# power_unit.net
KiCad netlist of a schematic drawn in Altium Designer
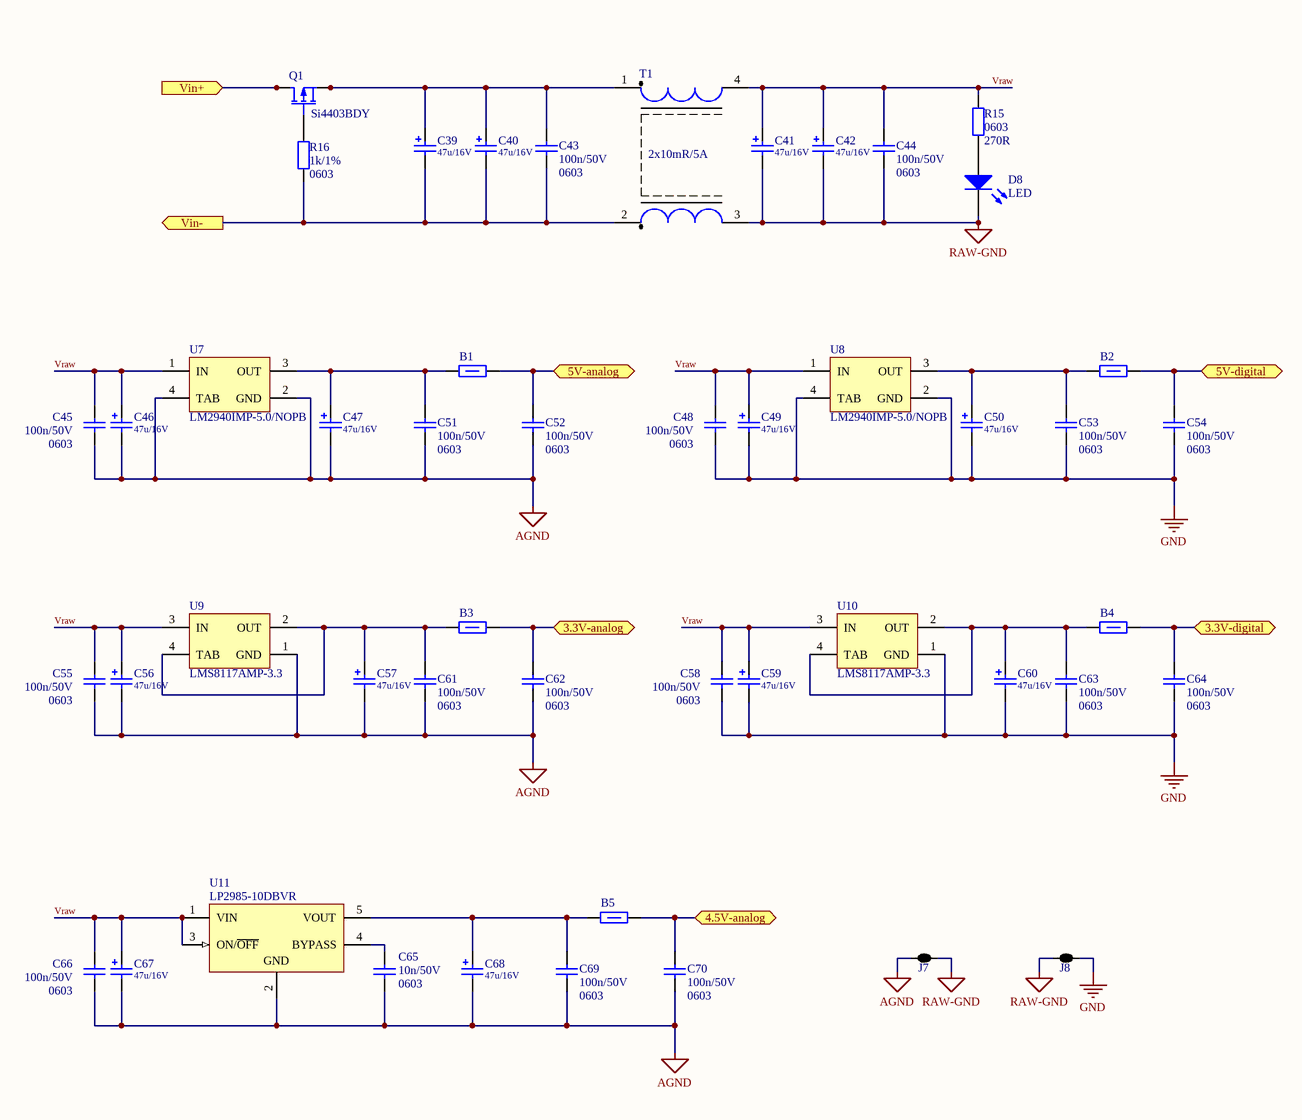
[diagram p0: power_unit.SchDoc]

(export (version "E")
  (design (tool "Eeschema 10.0.6"))
  (components
    (comp (ref "B1")
      (value "120R/100MHz")
      (footprint "SMD_FerriteBead_1206")
      (description "Ferrite bead, 1206, 0.02HM, 3.5A.")
      (fields (field (name "MANUFACTURER") "Murata") (field (name "MANUFACTURERPARTNUMBER") "BLM31PG121SH1L"))
      (libsource (lib "inductors") (part "BLM31PG121SH1L"))
    )
    (comp (ref "B2")
      (value "120R/100MHz")
      (footprint "SMD_FerriteBead_1206")
      (description "Ferrite bead, 1206, 0.02HM, 3.5A.")
      (fields (field (name "MANUFACTURER") "Murata") (field (name "MANUFACTURERPARTNUMBER") "BLM31PG121SH1L"))
      (libsource (lib "inductors") (part "BLM31PG121SH1L"))
    )
    (comp (ref "B3")
      (value "120R/100MHz")
      (footprint "SMD_FerriteBead_1206")
      (description "Ferrite bead, 1206, 0.02HM, 3.5A.")
      (fields (field (name "MANUFACTURER") "Murata") (field (name "MANUFACTURERPARTNUMBER") "BLM31PG121SH1L"))
      (libsource (lib "inductors") (part "BLM31PG121SH1L"))
    )
    (comp (ref "B4")
      (value "120R/100MHz")
      (footprint "SMD_FerriteBead_1206")
      (description "Ferrite bead, 1206, 0.02HM, 3.5A.")
      (fields (field (name "MANUFACTURER") "Murata") (field (name "MANUFACTURERPARTNUMBER") "BLM31PG121SH1L"))
      (libsource (lib "inductors") (part "BLM31PG121SH1L"))
    )
    (comp (ref "B5")
      (value "120R/100MHz")
      (footprint "SMD_FerriteBead_1206")
      (description "Ferrite bead, 1206, 0.02HM, 3.5A.")
      (fields (field (name "MANUFACTURER") "Murata") (field (name "MANUFACTURERPARTNUMBER") "BLM31PG121SH1L"))
      (libsource (lib "inductors") (part "BLM31PG121SH1L"))
    )
    (comp (ref "C39")
      (value "47u/16V")
      (footprint "Tantalum_cap_B")
      (description "Tantalum Capacitor")
      (libsource (lib "GG") (part "Cap Tantalum"))
    )
    (comp (ref "C40")
      (value "47u/16V")
      (footprint "Tantalum_cap_B")
      (description "Tantalum Capacitor")
      (libsource (lib "GG") (part "Cap Tantalum"))
    )
    (comp (ref "C41")
      (value "47u/16V")
      (footprint "Tantalum_cap_B")
      (description "Tantalum Capacitor")
      (libsource (lib "GG") (part "Cap Tantalum"))
    )
    (comp (ref "C42")
      (value "47u/16V")
      (footprint "Tantalum_cap_B")
      (description "Tantalum Capacitor")
      (libsource (lib "GG") (part "Cap Tantalum"))
    )
    (comp (ref "C43")
      (value "100n/50V")
      (footprint "SMD_Capacitor_0603")
      (description "Ceramic Cap Kemet COTS 100n/50V X7R 0603")
      (fields
        (field (name "MANUFACTURER") "Kemet")
        (field (name "MANUFACTURERPARTNUMBER") "C0603T104K5RALTU")
        (field (name "PACKAGE") "0603")
      )
      (libsource (lib "capacitors") (part "Cer_C0603T104K5RALTU"))
    )
    (comp (ref "C44")
      (value "100n/50V")
      (footprint "SMD_Capacitor_0603")
      (description "Ceramic Cap Kemet COTS 100n/50V X7R 0603")
      (fields
        (field (name "MANUFACTURER") "Kemet")
        (field (name "MANUFACTURERPARTNUMBER") "C0603T104K5RALTU")
        (field (name "PACKAGE") "0603")
      )
      (libsource (lib "capacitors") (part "Cer_C0603T104K5RALTU"))
    )
    (comp (ref "C45")
      (value "100n/50V")
      (footprint "SMD_Capacitor_0603")
      (description "Ceramic Cap Kemet COTS 100n/50V X7R 0603")
      (fields
        (field (name "MANUFACTURER") "Kemet")
        (field (name "MANUFACTURERPARTNUMBER") "C0603T104K5RALTU")
        (field (name "PACKAGE") "0603")
      )
      (libsource (lib "capacitors") (part "Cer_C0603T104K5RALTU"))
    )
    (comp (ref "C46")
      (value "47u/16V")
      (footprint "Tantalum_cap_B")
      (description "Tantalum Capacitor")
      (libsource (lib "GG") (part "Cap Tantalum"))
    )
    (comp (ref "C47")
      (value "47u/16V")
      (footprint "Tantalum_cap_B")
      (description "Tantalum Capacitor")
      (libsource (lib "GG") (part "Cap Tantalum"))
    )
    (comp (ref "C48")
      (value "100n/50V")
      (footprint "SMD_Capacitor_0603")
      (description "Ceramic Cap Kemet COTS 100n/50V X7R 0603")
      (fields
        (field (name "MANUFACTURER") "Kemet")
        (field (name "MANUFACTURERPARTNUMBER") "C0603T104K5RALTU")
        (field (name "PACKAGE") "0603")
      )
      (libsource (lib "capacitors") (part "Cer_C0603T104K5RALTU"))
    )
    (comp (ref "C49")
      (value "47u/16V")
      (footprint "Tantalum_cap_B")
      (description "Tantalum Capacitor")
      (libsource (lib "GG") (part "Cap Tantalum"))
    )
    (comp (ref "C50")
      (value "47u/16V")
      (footprint "Tantalum_cap_B")
      (description "Tantalum Capacitor")
      (libsource (lib "GG") (part "Cap Tantalum"))
    )
    (comp (ref "C51")
      (value "100n/50V")
      (footprint "SMD_Capacitor_0603")
      (description "Ceramic Cap Kemet COTS 100n/50V X7R 0603")
      (fields
        (field (name "MANUFACTURER") "Kemet")
        (field (name "MANUFACTURERPARTNUMBER") "C0603T104K5RALTU")
        (field (name "PACKAGE") "0603")
      )
      (libsource (lib "capacitors") (part "Cer_C0603T104K5RALTU"))
    )
    (comp (ref "C52")
      (value "100n/50V")
      (footprint "SMD_Capacitor_0603")
      (description "Ceramic Cap Kemet COTS 100n/50V X7R 0603")
      (fields
        (field (name "MANUFACTURER") "Kemet")
        (field (name "MANUFACTURERPARTNUMBER") "C0603T104K5RALTU")
        (field (name "PACKAGE") "0603")
      )
      (libsource (lib "capacitors") (part "Cer_C0603T104K5RALTU"))
    )
    (comp (ref "C53")
      (value "100n/50V")
      (footprint "SMD_Capacitor_0603")
      (description "Ceramic Cap Kemet COTS 100n/50V X7R 0603")
      (fields
        (field (name "MANUFACTURER") "Kemet")
        (field (name "MANUFACTURERPARTNUMBER") "C0603T104K5RALTU")
        (field (name "PACKAGE") "0603")
      )
      (libsource (lib "capacitors") (part "Cer_C0603T104K5RALTU"))
    )
    (comp (ref "C54")
      (value "100n/50V")
      (footprint "SMD_Capacitor_0603")
      (description "Ceramic Cap Kemet COTS 100n/50V X7R 0603")
      (fields
        (field (name "MANUFACTURER") "Kemet")
        (field (name "MANUFACTURERPARTNUMBER") "C0603T104K5RALTU")
        (field (name "PACKAGE") "0603")
      )
      (libsource (lib "capacitors") (part "Cer_C0603T104K5RALTU"))
    )
    (comp (ref "C55")
      (value "100n/50V")
      (footprint "SMD_Capacitor_0603")
      (description "Ceramic Cap Kemet COTS 100n/50V X7R 0603")
      (fields
        (field (name "MANUFACTURER") "Kemet")
        (field (name "MANUFACTURERPARTNUMBER") "C0603T104K5RALTU")
        (field (name "PACKAGE") "0603")
      )
      (libsource (lib "capacitors") (part "Cer_C0603T104K5RALTU"))
    )
    (comp (ref "C56")
      (value "47u/16V")
      (footprint "Tantalum_cap_B")
      (description "Tantalum Capacitor")
      (libsource (lib "GG") (part "Cap Tantalum"))
    )
    (comp (ref "C57")
      (value "47u/16V")
      (footprint "Tantalum_cap_B")
      (description "Tantalum Capacitor")
      (libsource (lib "GG") (part "Cap Tantalum"))
    )
    (comp (ref "C58")
      (value "100n/50V")
      (footprint "SMD_Capacitor_0603")
      (description "Ceramic Cap Kemet COTS 100n/50V X7R 0603")
      (fields
        (field (name "MANUFACTURER") "Kemet")
        (field (name "MANUFACTURERPARTNUMBER") "C0603T104K5RALTU")
        (field (name "PACKAGE") "0603")
      )
      (libsource (lib "capacitors") (part "Cer_C0603T104K5RALTU"))
    )
    (comp (ref "C59")
      (value "47u/16V")
      (footprint "Tantalum_cap_B")
      (description "Tantalum Capacitor")
      (libsource (lib "GG") (part "Cap Tantalum"))
    )
    (comp (ref "C60")
      (value "47u/16V")
      (footprint "Tantalum_cap_B")
      (description "Tantalum Capacitor")
      (libsource (lib "GG") (part "Cap Tantalum"))
    )
    (comp (ref "C61")
      (value "100n/50V")
      (footprint "SMD_Capacitor_0603")
      (description "Ceramic Cap Kemet COTS 100n/50V X7R 0603")
      (fields
        (field (name "MANUFACTURER") "Kemet")
        (field (name "MANUFACTURERPARTNUMBER") "C0603T104K5RALTU")
        (field (name "PACKAGE") "0603")
      )
      (libsource (lib "capacitors") (part "Cer_C0603T104K5RALTU"))
    )
    (comp (ref "C62")
      (value "100n/50V")
      (footprint "SMD_Capacitor_0603")
      (description "Ceramic Cap Kemet COTS 100n/50V X7R 0603")
      (fields
        (field (name "MANUFACTURER") "Kemet")
        (field (name "MANUFACTURERPARTNUMBER") "C0603T104K5RALTU")
        (field (name "PACKAGE") "0603")
      )
      (libsource (lib "capacitors") (part "Cer_C0603T104K5RALTU"))
    )
    (comp (ref "C63")
      (value "100n/50V")
      (footprint "SMD_Capacitor_0603")
      (description "Ceramic Cap Kemet COTS 100n/50V X7R 0603")
      (fields
        (field (name "MANUFACTURER") "Kemet")
        (field (name "MANUFACTURERPARTNUMBER") "C0603T104K5RALTU")
        (field (name "PACKAGE") "0603")
      )
      (libsource (lib "capacitors") (part "Cer_C0603T104K5RALTU"))
    )
    (comp (ref "C64")
      (value "100n/50V")
      (footprint "SMD_Capacitor_0603")
      (description "Ceramic Cap Kemet COTS 100n/50V X7R 0603")
      (fields
        (field (name "MANUFACTURER") "Kemet")
        (field (name "MANUFACTURERPARTNUMBER") "C0603T104K5RALTU")
        (field (name "PACKAGE") "0603")
      )
      (libsource (lib "capacitors") (part "Cer_C0603T104K5RALTU"))
    )
    (comp (ref "C65")
      (value "10n/50V")
      (footprint "SMD_Capacitor_0603")
      (description "Cap")
      (fields (field (name "PACKAGE") "0603"))
      (libsource (lib "capacitors") (part "Cap"))
    )
    (comp (ref "C66")
      (value "100n/50V")
      (footprint "SMD_Capacitor_0603")
      (description "Ceramic Cap Kemet COTS 100n/50V X7R 0603")
      (fields
        (field (name "MANUFACTURER") "Kemet")
        (field (name "MANUFACTURERPARTNUMBER") "C0603T104K5RALTU")
        (field (name "PACKAGE") "0603")
      )
      (libsource (lib "capacitors") (part "Cer_C0603T104K5RALTU"))
    )
    (comp (ref "C67")
      (value "47u/16V")
      (footprint "Tantalum_cap_B")
      (description "Tantalum Capacitor")
      (libsource (lib "GG") (part "Cap Tantalum"))
    )
    (comp (ref "C68")
      (value "47u/16V")
      (footprint "Tantalum_cap_B")
      (description "Tantalum Capacitor")
      (libsource (lib "GG") (part "Cap Tantalum"))
    )
    (comp (ref "C69")
      (value "100n/50V")
      (footprint "SMD_Capacitor_0603")
      (description "Ceramic Cap Kemet COTS 100n/50V X7R 0603")
      (fields
        (field (name "MANUFACTURER") "Kemet")
        (field (name "MANUFACTURERPARTNUMBER") "C0603T104K5RALTU")
        (field (name "PACKAGE") "0603")
      )
      (libsource (lib "capacitors") (part "Cer_C0603T104K5RALTU"))
    )
    (comp (ref "C70")
      (value "100n/50V")
      (footprint "SMD_Capacitor_0603")
      (description "Ceramic Cap Kemet COTS 100n/50V X7R 0603")
      (fields
        (field (name "MANUFACTURER") "Kemet")
        (field (name "MANUFACTURERPARTNUMBER") "C0603T104K5RALTU")
        (field (name "PACKAGE") "0603")
      )
      (libsource (lib "capacitors") (part "Cer_C0603T104K5RALTU"))
    )
    (comp (ref "D8")
      (value "LED")
      (footprint "LED 0805 RED")
      (description "Typical BLUE SiC LED")
      (fields (field (name "PUBLISHER") "Altium Limited"))
      (libsource (lib "Miscellaneous Devices") (part "LED3"))
    )
    (comp (ref "J7")
      (value "2 way net tie junction")
      (footprint "2way_MP")
      (libsource (lib "NetTieLib") (part "2way"))
    )
    (comp (ref "J8")
      (value "2 way net tie junction")
      (footprint "2way_MP")
      (libsource (lib "NetTieLib") (part "2way"))
    )
    (comp (ref "Q1")
      (value "Si4403BDY")
      (footprint "SOIC-8_M")
      (description "P-Channel 1.8 V (G-S) MOSFET")
      (libsource (lib "GG") (part "Si4403BDY"))
    )
    (comp (ref "R15")
      (value "0603")
      (footprint "SMD_Resistor_0603")
      (description "Resistor")
      (fields (field (name "ALTIUM_VALUE") "270R") (field (name "PUBLISHER") "Altium Limited"))
      (libsource (lib "Miscellaneous Devices") (part "Res2"))
    )
    (comp (ref "R16")
      (value "1k/1%")
      (footprint "SMD_Resistor_0603")
      (description "1k/1% Vishay CRCW 0603 Resistor. 100mW, 100ppm, 75V.")
      (fields
        (field (name "MANUFACTURER") "Vishay")
        (field (name "MANUFACTURERPARTNUMBER") "CRCW06031K00FKxxxx")
        (field (name "PACKAGE") "0603")
      )
      (libsource (lib "resistors") (part "CRCW06031K00FKxxxx"))
    )
    (comp (ref "T1")
      (value "2x10mR/5A")
      (footprint "TDK_ACM7060")
      (description "TDK ACM7060-301 Common Mode Choke")
      (fields
        (field (name "MANUFACTURER") "TDK")
        (field (name "MANUFACTURERPARTNUMBER") "ACM7060-301-2PL-TL01")
      )
      (libsource (lib "GG") (part "ACM7060-301-2PL-TL01"))
    )
    (comp (ref "U7")
      (value "LM2940IMP-5.0/NOPB")
      (footprint "MP04A_N")
      (description "1A Low Dropout Regulator, 4-pin SOT-223, Pb-Free")
      (fields (field (name "MANUFACTURER") "National Semiconductor"))
      (libsource (lib "National Semiconductor LDO") (part "LM2940IMP-5.0/NOPB"))
    )
    (comp (ref "U8")
      (value "LM2940IMP-5.0/NOPB")
      (footprint "MP04A_N")
      (description "1A Low Dropout Regulator, 4-pin SOT-223, Pb-Free")
      (fields (field (name "MANUFACTURER") "National Semiconductor"))
      (libsource (lib "National Semiconductor LDO") (part "LM2940IMP-5.0/NOPB"))
    )
    (comp (ref "U9")
      (value "LMS8117AMP-3.3")
      (footprint "MP04A_M")
      (description "1A Low-Dropout Linear Regulator, 4-pin SOT-223")
      (fields (field (name "MANUFACTURER") "National Semiconductor"))
      (libsource (lib "National Semiconductor LDO") (part "LMS8117AMP-3.3"))
    )
    (comp (ref "U10")
      (value "LMS8117AMP-3.3")
      (footprint "MP04A_M")
      (description "1A Low-Dropout Linear Regulator, 4-pin SOT-223")
      (fields (field (name "MANUFACTURER") "National Semiconductor"))
      (libsource (lib "National Semiconductor LDO") (part "LMS8117AMP-3.3"))
    )
    (comp (ref "U11")
      (value "LP2985-10DBVR")
      (footprint "TI-DBV5_N")
      (fields (field (name "MANUFACTURER") "Texas Instruments"))
      (libsource (lib "TI Power Management Linear Regulator Single Channel LDO (0-350mA)") (part "LP2985-10DBVR"))
    )
  )
  (nets
    (net (code "1") (name "/3.3V-analog") (class "Default")
      (node (ref "B3") (pin "2") (pinfunction "2_2") (pintype "passive"))
      (node (ref "C62") (pin "1") (pinfunction "1_1") (pintype "passive"))
    )
    (net (code "2") (name "/3.3V-digital") (class "Default")
      (node (ref "B4") (pin "2") (pinfunction "2_2") (pintype "passive"))
      (node (ref "C64") (pin "1") (pinfunction "1_1") (pintype "passive"))
    )
    (net (code "3") (name "/4.5V-analog") (class "Default")
      (node (ref "B5") (pin "2") (pinfunction "2_2") (pintype "passive"))
      (node (ref "C70") (pin "1") (pinfunction "1_1") (pintype "passive"))
    )
    (net (code "4") (name "/5V-analog") (class "Default")
      (node (ref "B1") (pin "2") (pinfunction "2_2") (pintype "passive"))
      (node (ref "C52") (pin "1") (pinfunction "1_1") (pintype "passive"))
    )
    (net (code "5") (name "/5V-digital") (class "Default")
      (node (ref "B2") (pin "2") (pinfunction "2_2") (pintype "passive"))
      (node (ref "C54") (pin "1") (pinfunction "1_1") (pintype "passive"))
    )
    (net (code "6") (name "/Vin+") (class "Default")
      (node (ref "Q1") (pin "5") (pinfunction "D_5") (pintype "passive"))
      (node (ref "Q1") (pin "6") (pinfunction "D_6") (pintype "passive"))
      (node (ref "Q1") (pin "7") (pinfunction "D_7") (pintype "passive"))
      (node (ref "Q1") (pin "8") (pinfunction "D_8") (pintype "passive"))
    )
    (net (code "7") (name "/Vin-") (class "Default")
      (node (ref "C39") (pin "2") (pinfunction "2_2") (pintype "passive"))
      (node (ref "C40") (pin "2") (pinfunction "2_2") (pintype "passive"))
      (node (ref "C43") (pin "2") (pinfunction "2_2") (pintype "passive"))
      (node (ref "R16") (pin "2") (pinfunction "2_2") (pintype "passive"))
      (node (ref "T1") (pin "2") (pinfunction "2_2") (pintype "passive"))
    )
    (net (code "8") (name "/Vraw") (class "Default")
      (node (ref "C41") (pin "1") (pinfunction "1_1") (pintype "passive"))
      (node (ref "C42") (pin "1") (pinfunction "1_1") (pintype "passive"))
      (node (ref "C44") (pin "1") (pinfunction "1_1") (pintype "passive"))
      (node (ref "C45") (pin "1") (pinfunction "1_1") (pintype "passive"))
      (node (ref "C46") (pin "1") (pinfunction "1_1") (pintype "passive"))
      (node (ref "C48") (pin "1") (pinfunction "1_1") (pintype "passive"))
      (node (ref "C49") (pin "1") (pinfunction "1_1") (pintype "passive"))
      (node (ref "C55") (pin "1") (pinfunction "1_1") (pintype "passive"))
      (node (ref "C56") (pin "1") (pinfunction "1_1") (pintype "passive"))
      (node (ref "C58") (pin "1") (pinfunction "1_1") (pintype "passive"))
      (node (ref "C59") (pin "1") (pinfunction "1_1") (pintype "passive"))
      (node (ref "C66") (pin "1") (pinfunction "1_1") (pintype "passive"))
      (node (ref "C67") (pin "1") (pinfunction "1_1") (pintype "passive"))
      (node (ref "R15") (pin "1") (pinfunction "1_1") (pintype "passive"))
      (node (ref "T1") (pin "4") (pinfunction "4_4") (pintype "passive"))
      (node (ref "U10") (pin "3") (pinfunction "IN_3") (pintype "power_in"))
      (node (ref "U11") (pin "1") (pinfunction "VIN_1") (pintype "power_in"))
      (node (ref "U11") (pin "3") (pinfunction "ON/~{OFF}_3") (pintype "input"))
      (node (ref "U7") (pin "1") (pinfunction "IN_1") (pintype "power_in"))
      (node (ref "U8") (pin "1") (pinfunction "IN_1") (pintype "power_in"))
      (node (ref "U9") (pin "3") (pinfunction "IN_3") (pintype "power_in"))
    )
    (net (code "9") (name "AGND") (class "Default")
      (node (ref "C45") (pin "2") (pinfunction "2_2") (pintype "passive"))
      (node (ref "C46") (pin "2") (pinfunction "2_2") (pintype "passive"))
      (node (ref "C47") (pin "2") (pinfunction "2_2") (pintype "passive"))
      (node (ref "C51") (pin "2") (pinfunction "2_2") (pintype "passive"))
      (node (ref "C52") (pin "2") (pinfunction "2_2") (pintype "passive"))
      (node (ref "C55") (pin "2") (pinfunction "2_2") (pintype "passive"))
      (node (ref "C56") (pin "2") (pinfunction "2_2") (pintype "passive"))
      (node (ref "C57") (pin "2") (pinfunction "2_2") (pintype "passive"))
      (node (ref "C61") (pin "2") (pinfunction "2_2") (pintype "passive"))
      (node (ref "C62") (pin "2") (pinfunction "2_2") (pintype "passive"))
      (node (ref "C65") (pin "2") (pinfunction "2_2") (pintype "passive"))
      (node (ref "C66") (pin "2") (pinfunction "2_2") (pintype "passive"))
      (node (ref "C67") (pin "2") (pinfunction "2_2") (pintype "passive"))
      (node (ref "C68") (pin "2") (pinfunction "2_2") (pintype "passive"))
      (node (ref "C69") (pin "2") (pinfunction "2_2") (pintype "passive"))
      (node (ref "C70") (pin "2") (pinfunction "2_2") (pintype "passive"))
      (node (ref "J7") (pin "2") (pinfunction "2_2") (pintype "passive"))
      (node (ref "U11") (pin "2") (pinfunction "GND_2") (pintype "power_in"))
      (node (ref "U7") (pin "2") (pinfunction "GND_2") (pintype "power_in"))
      (node (ref "U7") (pin "4") (pinfunction "TAB_4") (pintype "power_in"))
      (node (ref "U9") (pin "1") (pinfunction "GND_1") (pintype "power_in"))
    )
    (net (code "10") (name "GND") (class "Default")
      (node (ref "C48") (pin "2") (pinfunction "2_2") (pintype "passive"))
      (node (ref "C49") (pin "2") (pinfunction "2_2") (pintype "passive"))
      (node (ref "C50") (pin "2") (pinfunction "2_2") (pintype "passive"))
      (node (ref "C53") (pin "2") (pinfunction "2_2") (pintype "passive"))
      (node (ref "C54") (pin "2") (pinfunction "2_2") (pintype "passive"))
      (node (ref "C58") (pin "2") (pinfunction "2_2") (pintype "passive"))
      (node (ref "C59") (pin "2") (pinfunction "2_2") (pintype "passive"))
      (node (ref "C60") (pin "2") (pinfunction "2_2") (pintype "passive"))
      (node (ref "C63") (pin "2") (pinfunction "2_2") (pintype "passive"))
      (node (ref "C64") (pin "2") (pinfunction "2_2") (pintype "passive"))
      (node (ref "J8") (pin "1") (pinfunction "1_1") (pintype "passive"))
      (node (ref "U10") (pin "1") (pinfunction "GND_1") (pintype "power_in"))
      (node (ref "U8") (pin "2") (pinfunction "GND_2") (pintype "power_in"))
      (node (ref "U8") (pin "4") (pinfunction "TAB_4") (pintype "power_in"))
    )
    (net (code "11") (name "Net-(C39-Pad1)") (class "Default")
      (node (ref "C39") (pin "1") (pinfunction "1_1") (pintype "passive"))
      (node (ref "C40") (pin "1") (pinfunction "1_1") (pintype "passive"))
      (node (ref "C43") (pin "1") (pinfunction "1_1") (pintype "passive"))
      (node (ref "Q1") (pin "1") (pinfunction "S_1") (pintype "passive"))
      (node (ref "Q1") (pin "2") (pinfunction "S_2") (pintype "passive"))
      (node (ref "Q1") (pin "3") (pinfunction "S_3") (pintype "passive"))
      (node (ref "T1") (pin "1") (pinfunction "1_1") (pintype "passive"))
    )
    (net (code "12") (name "Net-(D8-A)") (class "Default")
      (node (ref "D8") (pin "1") (pinfunction "A_1") (pintype "passive"))
      (node (ref "R15") (pin "2") (pinfunction "2_2") (pintype "passive"))
    )
    (net (code "13") (name "Net-(Q1-G)") (class "Default")
      (node (ref "Q1") (pin "4") (pinfunction "G_4") (pintype "passive"))
      (node (ref "R16") (pin "1") (pinfunction "1_1") (pintype "passive"))
    )
    (net (code "14") (name "Net-(U7-OUT)") (class "Default")
      (node (ref "B1") (pin "1") (pinfunction "1_1") (pintype "passive"))
      (node (ref "C47") (pin "1") (pinfunction "1_1") (pintype "passive"))
      (node (ref "C51") (pin "1") (pinfunction "1_1") (pintype "passive"))
      (node (ref "U7") (pin "3") (pinfunction "OUT_3") (pintype "power_in"))
    )
    (net (code "15") (name "Net-(U8-OUT)") (class "Default")
      (node (ref "B2") (pin "1") (pinfunction "1_1") (pintype "passive"))
      (node (ref "C50") (pin "1") (pinfunction "1_1") (pintype "passive"))
      (node (ref "C53") (pin "1") (pinfunction "1_1") (pintype "passive"))
      (node (ref "U8") (pin "3") (pinfunction "OUT_3") (pintype "power_in"))
    )
    (net (code "16") (name "Net-(U9-OUT)") (class "Default")
      (node (ref "B3") (pin "1") (pinfunction "1_1") (pintype "passive"))
      (node (ref "C57") (pin "1") (pinfunction "1_1") (pintype "passive"))
      (node (ref "C61") (pin "1") (pinfunction "1_1") (pintype "passive"))
      (node (ref "U9") (pin "2") (pinfunction "OUT_2") (pintype "power_in"))
      (node (ref "U9") (pin "4") (pinfunction "TAB_4") (pintype "power_in"))
    )
    (net (code "17") (name "Net-(U10-OUT)") (class "Default")
      (node (ref "B4") (pin "1") (pinfunction "1_1") (pintype "passive"))
      (node (ref "C60") (pin "1") (pinfunction "1_1") (pintype "passive"))
      (node (ref "C63") (pin "1") (pinfunction "1_1") (pintype "passive"))
      (node (ref "U10") (pin "2") (pinfunction "OUT_2") (pintype "power_in"))
      (node (ref "U10") (pin "4") (pinfunction "TAB_4") (pintype "power_in"))
    )
    (net (code "18") (name "Net-(U11-BYPASS)") (class "Default")
      (node (ref "C65") (pin "1") (pinfunction "1_1") (pintype "passive"))
      (node (ref "U11") (pin "4") (pinfunction "BYPASS_4") (pintype "passive"))
    )
    (net (code "19") (name "Net-(U11-VOUT)") (class "Default")
      (node (ref "B5") (pin "1") (pinfunction "1_1") (pintype "passive"))
      (node (ref "C68") (pin "1") (pinfunction "1_1") (pintype "passive"))
      (node (ref "C69") (pin "1") (pinfunction "1_1") (pintype "passive"))
      (node (ref "U11") (pin "5") (pinfunction "VOUT_5") (pintype "power_in"))
    )
    (net (code "20") (name "RAW-GND") (class "Default")
      (node (ref "C41") (pin "2") (pinfunction "2_2") (pintype "passive"))
      (node (ref "C42") (pin "2") (pinfunction "2_2") (pintype "passive"))
      (node (ref "C44") (pin "2") (pinfunction "2_2") (pintype "passive"))
      (node (ref "D8") (pin "2") (pinfunction "K_2") (pintype "passive"))
      (node (ref "J7") (pin "1") (pinfunction "1_1") (pintype "passive"))
      (node (ref "J8") (pin "2") (pinfunction "2_2") (pintype "passive"))
      (node (ref "T1") (pin "3") (pinfunction "3_3") (pintype "passive"))
    )
  )
)
